# SerialUPDI_Programmer.net
KiCad netlist of a schematic drawn in EAGLE
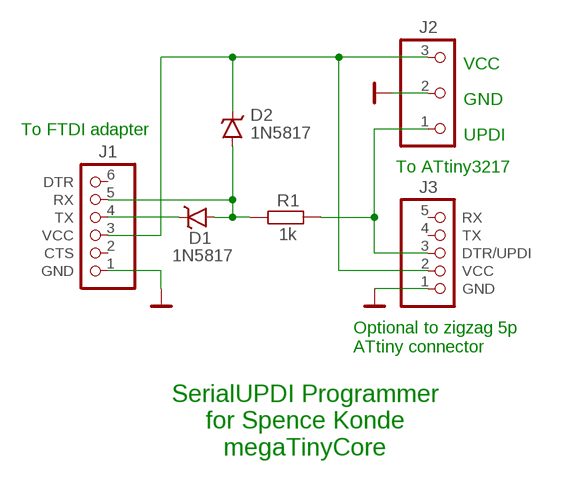
[diagram p0: schematic, sheet 1]

(export (version "E")
  (design (tool "Eeschema 10.0.6"))
  (components
    (comp (ref "D1")
      (value "1N5817")
      (footprint "eagle-import:SOD523")
      (libsource (lib "eagle-import") (part "SCHOTTKY-SMD-SOD523"))
    )
    (comp (ref "D2")
      (value "1N5817")
      (footprint "eagle-import:SOD523")
      (libsource (lib "eagle-import") (part "SCHOTTKY-SMD-SOD523"))
    )
    (comp (ref "J1")
      (value "6P")
      (footprint "eagle-import:1X06")
      (libsource (lib "eagle-import") (part "FTDIHEADER"))
    )
    (comp (ref "J2")
      (value "nc")
      (footprint "eagle-import:1X03")
      (libsource (lib "eagle-import") (part "CON-3P2.54"))
    )
    (comp (ref "J3")
      (value "nc")
      (footprint "eagle-import:FTDI-UPDI-5P")
      (libsource (lib "eagle-import") (part "ZIGZAG-FTDI-UPDI-5P{dblquote}"))
    )
    (comp (ref "R1")
      (value "1k")
      (footprint "eagle-import:0603")
      (libsource (lib "eagle-import") (part "SMD-R0603"))
    )
  )
  (nets
    (net (code "1") (name "GND") (class "Default")
      (node (ref "J1") (pin "1") (pinfunction "GND_1") (pintype "passive"))
      (node (ref "J2") (pin "2") (pinfunction "2_2") (pintype "passive"))
      (node (ref "J3") (pin "1") (pinfunction "GND_1") (pintype "passive"))
    )
    (net (code "2") (name "Net-(J1-RX)") (class "Default")
      (node (ref "D1") (pin "A") (pinfunction "A_A") (pintype "passive"))
      (node (ref "D2") (pin "A") (pinfunction "A_A") (pintype "passive"))
      (node (ref "J1") (pin "5") (pinfunction "RX_5") (pintype "passive"))
      (node (ref "R1") (pin "1") (pinfunction "1_1") (pintype "passive"))
    )
    (net (code "3") (name "Net-(J1-TX)") (class "Default")
      (node (ref "D1") (pin "C") (pinfunction "C_C") (pintype "passive"))
      (node (ref "J1") (pin "4") (pinfunction "TX_4") (pintype "passive"))
    )
    (net (code "4") (name "Net-(J1-VCC)") (class "Default")
      (node (ref "D2") (pin "C") (pinfunction "C_C") (pintype "passive"))
      (node (ref "J1") (pin "3") (pinfunction "VCC_3") (pintype "passive"))
      (node (ref "J2") (pin "3") (pinfunction "3_3") (pintype "passive"))
      (node (ref "J3") (pin "2") (pinfunction "VCC_2") (pintype "passive"))
    )
    (net (code "5") (name "Net-(J3-DTR{slash}UPDI)") (class "Default")
      (node (ref "J2") (pin "1") (pinfunction "1_1") (pintype "passive"))
      (node (ref "J3") (pin "3") (pinfunction "DTR/UPDI_3") (pintype "passive"))
      (node (ref "R1") (pin "2") (pinfunction "2_2") (pintype "passive"))
    )
    (net (code "6") (name "unconnected-(J1-CTS-Pad2)") (class "Default")
      (node (ref "J1") (pin "2") (pinfunction "CTS_2") (pintype "passive"))
    )
    (net (code "7") (name "unconnected-(J1-DTR-Pad6)") (class "Default")
      (node (ref "J1") (pin "6") (pinfunction "DTR_6") (pintype "passive"))
    )
    (net (code "8") (name "unconnected-(J3-RX-Pad5)") (class "Default")
      (node (ref "J3") (pin "5") (pinfunction "RX_5") (pintype "passive"))
    )
    (net (code "9") (name "unconnected-(J3-TX-Pad4)") (class "Default")
      (node (ref "J3") (pin "4") (pinfunction "TX_4") (pintype "passive"))
    )
  )
)
